# 3_3V_and_1_8V_Load.net
KiCad netlist of a schematic drawn in Altium Designer
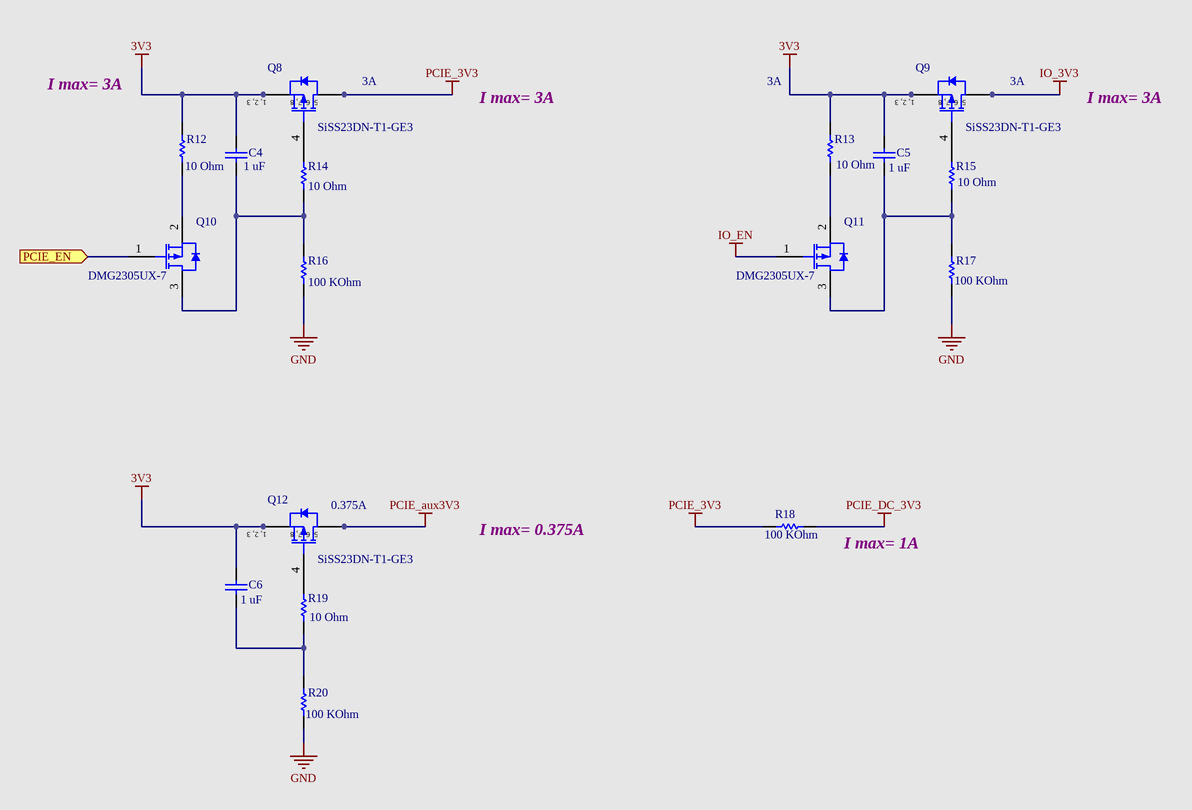
[diagram p0: 3.3V_and_1.8V_Load.SchDoc]

(export (version "E")
  (design (tool "Eeschema 10.0.6"))
  (components
    (comp (ref "C4")
      (value "CGB2A1X5R1E105K033BC")
      (footprint "CAPC1005X33X10LL5")
      (description "Chip Capacitor, 1 uF, +/- 10%, 25 V, -55 to 85 degC, 0402 (1005 Metric), RoHS, Tape and Reel")
      (fields (field (name "TOLERANCE") "10%") (field (name "CAPACITANCE") "1 uF"))
      (libsource (lib "Altium Content Vault") (part "CAP-NP-2"))
    )
    (comp (ref "C5")
      (value "CGB2A1X5R1E105K033BC")
      (footprint "CAPC1005X33X10LL5")
      (description "Chip Capacitor, 1 uF, +/- 10%, 25 V, -55 to 85 degC, 0402 (1005 Metric), RoHS, Tape and Reel")
      (fields (field (name "TOLERANCE") "10%") (field (name "CAPACITANCE") "1 uF"))
      (libsource (lib "Altium Content Vault") (part "CAP-NP-2"))
    )
    (comp (ref "C6")
      (value "CGB2A1X5R1E105K033BC")
      (footprint "CAPC1005X33X10LL5")
      (description "Chip Capacitor, 1 uF, +/- 10%, 25 V, -55 to 85 degC, 0402 (1005 Metric), RoHS, Tape and Reel")
      (fields (field (name "TOLERANCE") "10%") (field (name "CAPACITANCE") "1 uF"))
      (libsource (lib "Altium Content Vault") (part "CAP-NP-2"))
    )
    (comp (ref "Q8")
      (value "SiSS23DN-T1-GE3")
      (footprint "VISH-PPAK1212-8S_V")
      (description "P-Channel MOSFET, 20 V, -50 to 150 degC, 8-Pin SMD (PPAK1212-8S), RoHS, Tape and Reel")
      (libsource (lib "Altium Content Vault") (part "PEMOS-SSSGDDDD-8"))
    )
    (comp (ref "Q9")
      (value "SiSS23DN-T1-GE3")
      (footprint "VISH-PPAK1212-8S_V")
      (description "P-Channel MOSFET, 20 V, -50 to 150 degC, 8-Pin SMD (PPAK1212-8S), RoHS, Tape and Reel")
      (libsource (lib "Altium Content Vault") (part "PEMOS-SSSGDDDD-8"))
    )
    (comp (ref "Q10")
      (value "DMG2305UX-7")
      (footprint "DIOD-SOT23-3_A_V")
      (description "P-Channel Enhancement Mode MOSFET, 20 V, -55 to 150 degC, 3-Pin SOT23, RoHS, Tape and Reel")
      (fields (field (name "MANUFACTURER") "Diodes Inc"))
      (libsource (lib "Altium Content Vault") (part "CMP-1693-00002-1"))
    )
    (comp (ref "Q11")
      (value "DMG2305UX-7")
      (footprint "DIOD-SOT23-3_A_V")
      (description "P-Channel Enhancement Mode MOSFET, 20 V, -55 to 150 degC, 3-Pin SOT23, RoHS, Tape and Reel")
      (fields (field (name "MANUFACTURER") "Diodes Inc"))
      (libsource (lib "Altium Content Vault") (part "CMP-1693-00002-1"))
    )
    (comp (ref "Q12")
      (value "SiSS23DN-T1-GE3")
      (footprint "VISH-PPAK1212-8S_V")
      (description "P-Channel MOSFET, 20 V, -50 to 150 degC, 8-Pin SMD (PPAK1212-8S), RoHS, Tape and Reel")
      (libsource (lib "Altium Content Vault") (part "PEMOS-SSSGDDDD-8"))
    )
    (comp (ref "R12")
      (value "ERJ-2RKF10R0X")
      (footprint "RESC1005X40X25LL05T05")
      (description "Chip Resistor, 10 Ohm, +/- 1%, 100 mW, -55 to 155 degC, 0402 (1005 Metric), RoHS, Tape and Reel")
      (fields
        (field (name "RESISTANCE") "10 Ohm")
        (field (name "TOLERANCE") "1%")
        (field (name "MANUFACTURER") "Basic Passives")
      )
      (libsource (lib "Altium Content Vault") (part "RES-2"))
    )
    (comp (ref "R13")
      (value "ERJ-2RKF10R0X")
      (footprint "RESC1005X40X25LL05T05")
      (description "Chip Resistor, 10 Ohm, +/- 1%, 100 mW, -55 to 155 degC, 0402 (1005 Metric), RoHS, Tape and Reel")
      (fields
        (field (name "RESISTANCE") "10 Ohm")
        (field (name "TOLERANCE") "1%")
        (field (name "MANUFACTURER") "Basic Passives")
      )
      (libsource (lib "Altium Content Vault") (part "RES-2"))
    )
    (comp (ref "R14")
      (value "ERJ-2RKF10R0X")
      (footprint "RESC1005X40X25LL05T05")
      (description "Chip Resistor, 10 Ohm, +/- 1%, 100 mW, -55 to 155 degC, 0402 (1005 Metric), RoHS, Tape and Reel")
      (fields
        (field (name "RESISTANCE") "10 Ohm")
        (field (name "TOLERANCE") "1%")
        (field (name "MANUFACTURER") "Basic Passives")
      )
      (libsource (lib "Altium Content Vault") (part "RES-2"))
    )
    (comp (ref "R15")
      (value "ERJ-2RKF10R0X")
      (footprint "RESC1005X40X25LL05T05")
      (description "Chip Resistor, 10 Ohm, +/- 1%, 100 mW, -55 to 155 degC, 0402 (1005 Metric), RoHS, Tape and Reel")
      (fields
        (field (name "RESISTANCE") "10 Ohm")
        (field (name "TOLERANCE") "1%")
        (field (name "MANUFACTURER") "Basic Passives")
      )
      (libsource (lib "Altium Content Vault") (part "RES-2"))
    )
    (comp (ref "R16")
      (value "ERJ-2RKF1003X")
      (footprint "RESC1005X40X25LL05T05")
      (description "Chip Resistor, 100 KOhm, +/- 1%, 100 mW, -55 to 155 degC, 0402 (1005 Metric), RoHS, Tape and Reel")
      (fields
        (field (name "RESISTANCE") "100 KOhm")
        (field (name "TOLERANCE") "1%")
        (field (name "MANUFACTURER") "Basic Passives")
      )
      (libsource (lib "Altium Content Vault") (part "RES-2"))
    )
    (comp (ref "R17")
      (value "ERJ-2RKF1003X")
      (footprint "RESC1005X40X25LL05T05")
      (description "Chip Resistor, 100 KOhm, +/- 1%, 100 mW, -55 to 155 degC, 0402 (1005 Metric), RoHS, Tape and Reel")
      (fields
        (field (name "RESISTANCE") "100 KOhm")
        (field (name "TOLERANCE") "1%")
        (field (name "MANUFACTURER") "Basic Passives")
      )
      (libsource (lib "Altium Content Vault") (part "RES-2"))
    )
    (comp (ref "R18")
      (value "ERJ-2RKF1003X")
      (footprint "RESC1005X40X25LL05T05")
      (description "Chip Resistor, 100 KOhm, +/- 1%, 100 mW, -55 to 155 degC, 0402 (1005 Metric), RoHS, Tape and Reel")
      (fields
        (field (name "TOLERANCE") "1%")
        (field (name "RESISTANCE") "100 KOhm")
        (field (name "MANUFACTURER") "Basic Passives")
      )
      (libsource (lib "Altium Content Vault") (part "RES-2"))
    )
    (comp (ref "R19")
      (value "ERJ-2RKF10R0X")
      (footprint "RESC1005X40X25LL05T05")
      (description "Chip Resistor, 10 Ohm, +/- 1%, 100 mW, -55 to 155 degC, 0402 (1005 Metric), RoHS, Tape and Reel")
      (fields
        (field (name "RESISTANCE") "10 Ohm")
        (field (name "TOLERANCE") "1%")
        (field (name "MANUFACTURER") "Basic Passives")
      )
      (libsource (lib "Altium Content Vault") (part "RES-2"))
    )
    (comp (ref "R20")
      (value "ERJ-2RKF1003X")
      (footprint "RESC1005X40X25LL05T05")
      (description "Chip Resistor, 100 KOhm, +/- 1%, 100 mW, -55 to 155 degC, 0402 (1005 Metric), RoHS, Tape and Reel")
      (fields
        (field (name "RESISTANCE") "100 KOhm")
        (field (name "TOLERANCE") "1%")
        (field (name "MANUFACTURER") "Basic Passives")
      )
      (libsource (lib "Altium Content Vault") (part "RES-2"))
    )
  )
  (nets
    (net (code "1") (name "/PCIE_EN") (class "Default")
      (node (ref "Q10") (pin "1") (pinfunction "GATE_1") (pintype "passive"))
    )
    (net (code "2") (name "3V3") (class "Default")
      (node (ref "C4") (pin "2") (pinfunction "2_2") (pintype "passive"))
      (node (ref "C5") (pin "2") (pinfunction "2_2") (pintype "passive"))
      (node (ref "C6") (pin "2") (pinfunction "2_2") (pintype "passive"))
      (node (ref "Q12") (pin "1") (pinfunction "S_1") (pintype "passive"))
      (node (ref "Q12") (pin "2") (pinfunction "S_2") (pintype "passive"))
      (node (ref "Q12") (pin "3") (pinfunction "S_3") (pintype "passive"))
      (node (ref "Q8") (pin "1") (pinfunction "S_1") (pintype "passive"))
      (node (ref "Q8") (pin "2") (pinfunction "S_2") (pintype "passive"))
      (node (ref "Q8") (pin "3") (pinfunction "S_3") (pintype "passive"))
      (node (ref "Q9") (pin "1") (pinfunction "S_1") (pintype "passive"))
      (node (ref "Q9") (pin "2") (pinfunction "S_2") (pintype "passive"))
      (node (ref "Q9") (pin "3") (pinfunction "S_3") (pintype "passive"))
      (node (ref "R12") (pin "2") (pinfunction "2_2") (pintype "passive"))
      (node (ref "R13") (pin "2") (pinfunction "2_2") (pintype "passive"))
    )
    (net (code "3") (name "GND") (class "Default")
      (node (ref "R16") (pin "1") (pinfunction "1_1") (pintype "passive"))
      (node (ref "R17") (pin "1") (pinfunction "1_1") (pintype "passive"))
      (node (ref "R20") (pin "1") (pinfunction "1_1") (pintype "passive"))
    )
    (net (code "4") (name "IO_3V3") (class "Default")
      (node (ref "Q9") (pin "5") (pinfunction "D_5") (pintype "passive"))
      (node (ref "Q9") (pin "6") (pinfunction "D_6") (pintype "passive"))
      (node (ref "Q9") (pin "7") (pinfunction "D_7") (pintype "passive"))
      (node (ref "Q9") (pin "8") (pinfunction "D_8") (pintype "passive"))
    )
    (net (code "5") (name "IO_EN") (class "Default")
      (node (ref "Q11") (pin "1") (pinfunction "GATE_1") (pintype "passive"))
    )
    (net (code "6") (name "Net-(C6-Pad1)") (class "Default")
      (node (ref "C6") (pin "1") (pinfunction "1_1") (pintype "passive"))
      (node (ref "R19") (pin "1") (pinfunction "1_1") (pintype "passive"))
      (node (ref "R20") (pin "2") (pinfunction "2_2") (pintype "passive"))
    )
    (net (code "7") (name "Net-(Q8-G)") (class "Default")
      (node (ref "Q8") (pin "4") (pinfunction "G_4") (pintype "passive"))
      (node (ref "R14") (pin "2") (pinfunction "2_2") (pintype "passive"))
    )
    (net (code "8") (name "Net-(Q9-G)") (class "Default")
      (node (ref "Q9") (pin "4") (pinfunction "G_4") (pintype "passive"))
      (node (ref "R15") (pin "2") (pinfunction "2_2") (pintype "passive"))
    )
    (net (code "9") (name "Net-(Q10-DRAIN)") (class "Default")
      (node (ref "C4") (pin "1") (pinfunction "1_1") (pintype "passive"))
      (node (ref "Q10") (pin "3") (pinfunction "DRAIN_3") (pintype "passive"))
      (node (ref "R14") (pin "1") (pinfunction "1_1") (pintype "passive"))
      (node (ref "R16") (pin "2") (pinfunction "2_2") (pintype "passive"))
    )
    (net (code "10") (name "Net-(Q10-SOURCE)") (class "Default")
      (node (ref "Q10") (pin "2") (pinfunction "SOURCE_2") (pintype "passive"))
      (node (ref "R12") (pin "1") (pinfunction "1_1") (pintype "passive"))
    )
    (net (code "11") (name "Net-(Q11-DRAIN)") (class "Default")
      (node (ref "C5") (pin "1") (pinfunction "1_1") (pintype "passive"))
      (node (ref "Q11") (pin "3") (pinfunction "DRAIN_3") (pintype "passive"))
      (node (ref "R15") (pin "1") (pinfunction "1_1") (pintype "passive"))
      (node (ref "R17") (pin "2") (pinfunction "2_2") (pintype "passive"))
    )
    (net (code "12") (name "Net-(Q11-SOURCE)") (class "Default")
      (node (ref "Q11") (pin "2") (pinfunction "SOURCE_2") (pintype "passive"))
      (node (ref "R13") (pin "1") (pinfunction "1_1") (pintype "passive"))
    )
    (net (code "13") (name "Net-(Q12-G)") (class "Default")
      (node (ref "Q12") (pin "4") (pinfunction "G_4") (pintype "passive"))
      (node (ref "R19") (pin "2") (pinfunction "2_2") (pintype "passive"))
    )
    (net (code "14") (name "PCIE_3V3") (class "Default")
      (node (ref "Q8") (pin "5") (pinfunction "D_5") (pintype "passive"))
      (node (ref "Q8") (pin "6") (pinfunction "D_6") (pintype "passive"))
      (node (ref "Q8") (pin "7") (pinfunction "D_7") (pintype "passive"))
      (node (ref "Q8") (pin "8") (pinfunction "D_8") (pintype "passive"))
      (node (ref "R18") (pin "2") (pinfunction "2_2") (pintype "passive"))
    )
    (net (code "15") (name "PCIE_DC_3V3") (class "Default")
      (node (ref "R18") (pin "1") (pinfunction "1_1") (pintype "passive"))
    )
    (net (code "16") (name "PCIE_aux3V3") (class "Default")
      (node (ref "Q12") (pin "5") (pinfunction "D_5") (pintype "passive"))
      (node (ref "Q12") (pin "6") (pinfunction "D_6") (pintype "passive"))
      (node (ref "Q12") (pin "7") (pinfunction "D_7") (pintype "passive"))
      (node (ref "Q12") (pin "8") (pinfunction "D_8") (pintype "passive"))
    )
  )
)
